# Power_Distribution_-_Power_Path_AUX_MOSF.net
KiCad netlist of a schematic drawn in Altium Designer
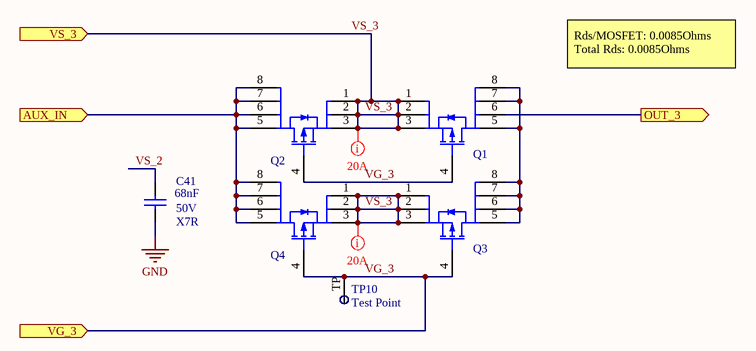
[diagram p0: Power Distribution - Power Path AUX MOSFET.SchDoc]

(export (version "E")
  (design (tool "Eeschema 10.0.6"))
  (components
    (comp (ref "C41")
      (value "68nF")
      (footprint "CAP, 0603")
      (description "0.068µF 50V Ceramic Capacitor X7R 0603 (1608 Metric) 0.063\" L x 0.032\" W (1.60mm x 0.80mm)")
      (fields
        (field (name "MANUFACTURER") "Murata")
        (field (name "MANUFACTURER PART NUMBER") "GCM188R71H683KA57D")
        (field (name "VOLTAGE RATING") "50V")
        (field (name "DIELECTRIC") "X7R")
      )
      (libsource (lib "Schematic Diagrams") (part "CAP CER 0.068UF 10% 50V X7R 0603"))
    )
    (comp (ref "Q1")
      (value "MOSFET P-CH PWR56 40V 4.9 MOHM")
      (footprint "PMOS PWR56 40V 4.9 MOHM")
      (description "P-Channel 16V 2.5A (Ta) 650mW (Ta) Surface Mount X2-DFN2015-3")
      (libsource (lib "Schematic Diagrams") (part "MOSFET P-CH PWR56 40V 4.9 MOHM"))
    )
    (comp (ref "Q2")
      (value "MOSFET P-CH PWR56 40V 4.9 MOHM")
      (footprint "PMOS PWR56 40V 4.9 MOHM")
      (description "P-Channel 16V 2.5A (Ta) 650mW (Ta) Surface Mount X2-DFN2015-3")
      (libsource (lib "Schematic Diagrams") (part "MOSFET P-CH PWR56 40V 4.9 MOHM"))
    )
    (comp (ref "Q3")
      (value "MOSFET P-CH PWR56 40V 4.9 MOHM")
      (footprint "PMOS PWR56 40V 4.9 MOHM")
      (description "P-Channel 16V 2.5A (Ta) 650mW (Ta) Surface Mount X2-DFN2015-3")
      (libsource (lib "Schematic Diagrams") (part "MOSFET P-CH PWR56 40V 4.9 MOHM"))
    )
    (comp (ref "Q4")
      (value "MOSFET P-CH PWR56 40V 4.9 MOHM")
      (footprint "PMOS PWR56 40V 4.9 MOHM")
      (description "P-Channel 16V 2.5A (Ta) 650mW (Ta) Surface Mount X2-DFN2015-3")
      (libsource (lib "Schematic Diagrams") (part "MOSFET P-CH PWR56 40V 4.9 MOHM"))
    )
    (comp (ref "TP10")
      (value "Test Point")
      (footprint "Test Point")
      (libsource (lib "Schematic Diagrams") (part "Test Point"))
    )
  )
  (nets
    (net (code "1") (name "/AUX_IN") (class "Default")
      (node (ref "Q2") (pin "5") (pinfunction "D_5") (pintype "passive"))
      (node (ref "Q2") (pin "6") (pinfunction "D_6") (pintype "passive"))
      (node (ref "Q2") (pin "7") (pinfunction "D_7") (pintype "passive"))
      (node (ref "Q2") (pin "8") (pinfunction "D_8") (pintype "passive"))
      (node (ref "Q4") (pin "5") (pinfunction "D_5") (pintype "passive"))
      (node (ref "Q4") (pin "6") (pinfunction "D_6") (pintype "passive"))
      (node (ref "Q4") (pin "7") (pinfunction "D_7") (pintype "passive"))
      (node (ref "Q4") (pin "8") (pinfunction "D_8") (pintype "passive"))
    )
    (net (code "2") (name "/OUT_3") (class "Default")
      (node (ref "Q1") (pin "6") (pinfunction "D_6") (pintype "passive"))
    )
    (net (code "3") (name "/VG_3") (class "Default")
      (node (ref "Q1") (pin "4") (pinfunction "G_4") (pintype "passive"))
      (node (ref "Q2") (pin "4") (pinfunction "G_4") (pintype "passive"))
      (node (ref "Q3") (pin "4") (pinfunction "G_4") (pintype "passive"))
      (node (ref "Q4") (pin "4") (pinfunction "G_4") (pintype "passive"))
      (node (ref "TP10") (pin "TP") (pinfunction "1_TP") (pintype "passive"))
    )
    (net (code "4") (name "/VS_2") (class "Default")
      (node (ref "C41") (pin "1") (pinfunction "1_1") (pintype "passive"))
    )
    (net (code "5") (name "/VS_3") (class "Default")
      (node (ref "Q1") (pin "1") (pinfunction "S_1") (pintype "passive"))
      (node (ref "Q1") (pin "2") (pinfunction "S_2") (pintype "passive"))
      (node (ref "Q1") (pin "3") (pinfunction "S_3") (pintype "passive"))
      (node (ref "Q2") (pin "1") (pinfunction "S_1") (pintype "passive"))
      (node (ref "Q2") (pin "2") (pinfunction "S_2") (pintype "passive"))
      (node (ref "Q2") (pin "3") (pinfunction "S_3") (pintype "passive"))
      (node (ref "Q3") (pin "1") (pinfunction "S_1") (pintype "passive"))
      (node (ref "Q3") (pin "2") (pinfunction "S_2") (pintype "passive"))
      (node (ref "Q3") (pin "3") (pinfunction "S_3") (pintype "passive"))
      (node (ref "Q4") (pin "1") (pinfunction "S_1") (pintype "passive"))
      (node (ref "Q4") (pin "2") (pinfunction "S_2") (pintype "passive"))
      (node (ref "Q4") (pin "3") (pinfunction "S_3") (pintype "passive"))
    )
    (net (code "6") (name "GND") (class "Default")
      (node (ref "C41") (pin "2") (pinfunction "2_2") (pintype "passive"))
    )
    (net (code "7") (name "Net-(Q1-D-Pad5)") (class "Default")
      (node (ref "Q1") (pin "5") (pinfunction "D_5") (pintype "passive"))
      (node (ref "Q1") (pin "7") (pinfunction "D_7") (pintype "passive"))
      (node (ref "Q1") (pin "8") (pinfunction "D_8") (pintype "passive"))
      (node (ref "Q3") (pin "5") (pinfunction "D_5") (pintype "passive"))
      (node (ref "Q3") (pin "6") (pinfunction "D_6") (pintype "passive"))
      (node (ref "Q3") (pin "7") (pinfunction "D_7") (pintype "passive"))
      (node (ref "Q3") (pin "8") (pinfunction "D_8") (pintype "passive"))
    )
  )
)
